# Sensor_Board_v2.net
KiCad netlist of a schematic drawn in EAGLE
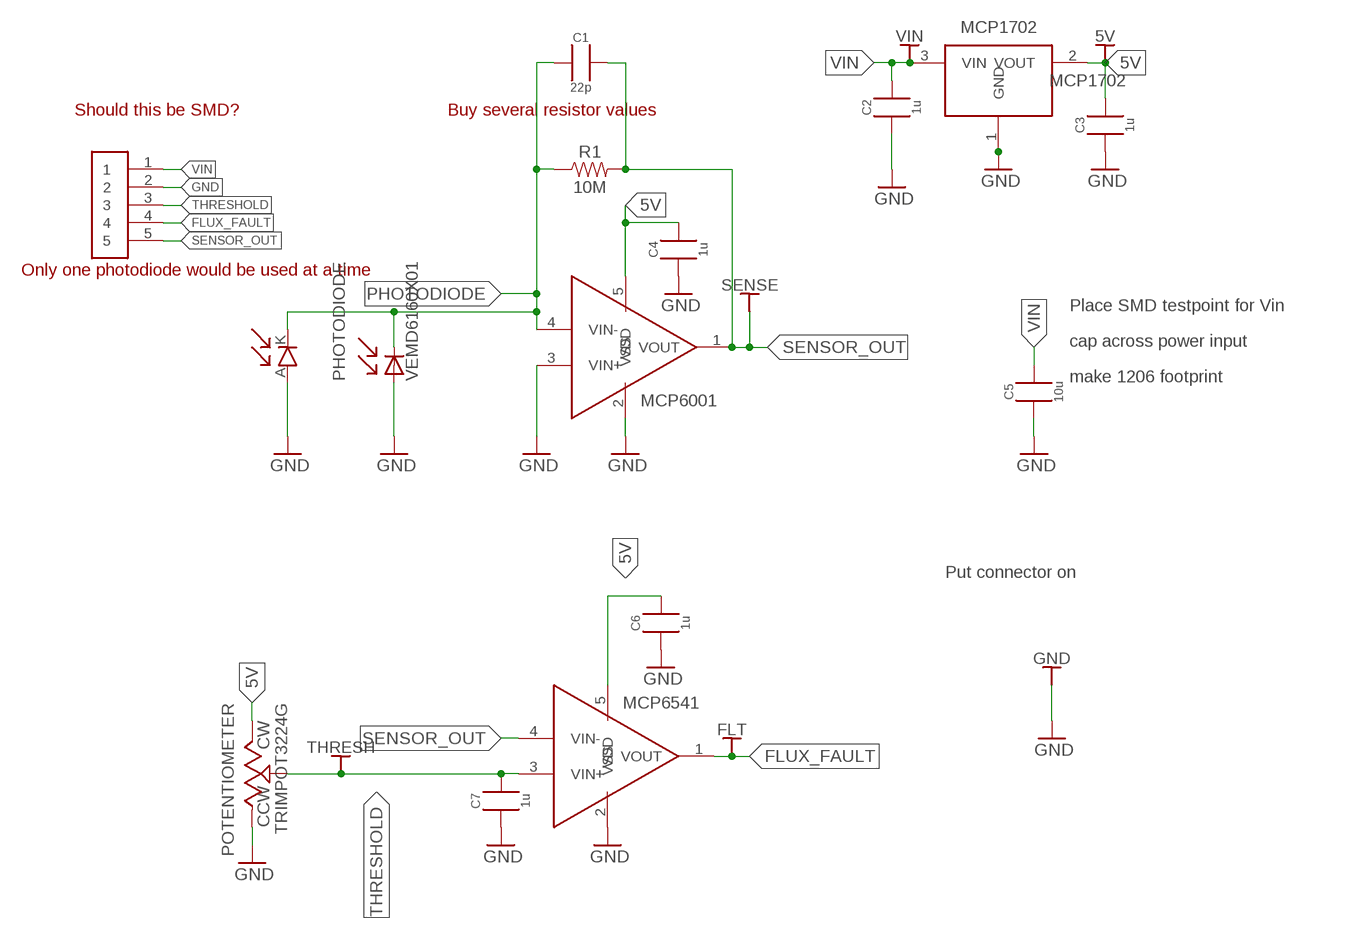
[diagram p0: schematic, sheet 1]

(export (version "E")
  (design (tool "Eeschema 10.0.6"))
  (components
    (comp (ref "5V")
      (value "TEST_POINT5015")
      (footprint "eagle-import:5015")
      (libsource (lib "eagle-import") (part "TEST_POINT5015"))
    )
    (comp (ref "C1")
      (value "22p")
      (footprint "eagle-import:0805_C")
      (libsource (lib "eagle-import") (part "CAP0805C"))
    )
    (comp (ref "C2")
      (value "1u")
      (footprint "eagle-import:0805_C")
      (libsource (lib "eagle-import") (part "CAP0805C"))
    )
    (comp (ref "C3")
      (value "1u")
      (footprint "eagle-import:0805_B")
      (libsource (lib "eagle-import") (part "CAP805B"))
    )
    (comp (ref "C4")
      (value "1u")
      (footprint "eagle-import:0805_B")
      (libsource (lib "eagle-import") (part "CAP805B"))
    )
    (comp (ref "C5")
      (value "10u")
      (footprint "eagle-import:1206_A")
      (libsource (lib "eagle-import") (part "CAP1206A"))
    )
    (comp (ref "C6")
      (value "1u")
      (footprint "eagle-import:0805_B")
      (libsource (lib "eagle-import") (part "CAP805B"))
    )
    (comp (ref "C7")
      (value "1u")
      (footprint "eagle-import:0805_B")
      (libsource (lib "eagle-import") (part "CAP805B"))
    )
    (comp (ref "FLT")
      (value "TEST_POINT5015")
      (footprint "eagle-import:5015")
      (libsource (lib "eagle-import") (part "TEST_POINT5015"))
    )
    (comp (ref "GND")
      (value "TEST_POINT5015")
      (footprint "eagle-import:5015")
      (libsource (lib "eagle-import") (part "TEST_POINT5015"))
    )
    (comp (ref "MCP1702")
      (value "MCP1702")
      (footprint "eagle-import:SOT23A(CB)")
      (libsource (lib "eagle-import") (part "MCP1702"))
    )
    (comp (ref "MCP6001")
      (value "MCP6001MCP6001")
      (footprint "eagle-import:SOT23(OT)")
      (libsource (lib "eagle-import") (part "MCP6001MCP6001"))
    )
    (comp (ref "MCP6541")
      (value "MCP6541")
      (footprint "eagle-import:SOT23(OT)")
      (libsource (lib "eagle-import") (part "MCP6541"))
    )
    (comp (ref "PHOTODIODE")
      (value "VEMD6160X01")
      (footprint "eagle-import:VEMD6160X01")
      (libsource (lib "eagle-import") (part "VEMD6160X01"))
    )
    (comp (ref "R1")
      (value "10M")
      (footprint "eagle-import:1206")
      (libsource (lib "eagle-import") (part "RESISTOR1206"))
    )
    (comp (ref "SENSE")
      (value "TEST_POINT5015")
      (footprint "eagle-import:5015")
      (libsource (lib "eagle-import") (part "TEST_POINT5015"))
    )
    (comp (ref "THRESH")
      (value "TEST_POINT5015")
      (footprint "eagle-import:5015")
      (libsource (lib "eagle-import") (part "TEST_POINT5015"))
    )
    (comp (ref "TRIMPOT3224G")
      (value "POTENTIOMETER")
      (footprint "eagle-import:3224G")
      (libsource (lib "eagle-import") (part "POTENTIOMETER"))
    )
    (comp (ref "U$1")
      (value "M05OSTVN05")
      (footprint "eagle-import:OSTVN05")
      (libsource (lib "eagle-import") (part "M05OSTVN05"))
    )
    (comp (ref "U$2")
      (value "PHOTODIODE")
      (footprint "eagle-import:LTR-516AD")
      (libsource (lib "eagle-import") (part "PHOTODIODE"))
    )
    (comp (ref "VIN")
      (value "TEST_POINT5015")
      (footprint "eagle-import:5015")
      (libsource (lib "eagle-import") (part "TEST_POINT5015"))
    )
  )
  (nets
    (net (code "1") (name "5V") (class "Default")
      (node (ref "5V") (pin "1") (pinfunction "P$1_1") (pintype "bidirectional"))
      (node (ref "C3") (pin "2") (pinfunction "2_2") (pintype "bidirectional"))
      (node (ref "C4") (pin "2") (pinfunction "2_2") (pintype "bidirectional"))
      (node (ref "C6") (pin "2") (pinfunction "2_2") (pintype "bidirectional"))
      (node (ref "MCP1702") (pin "2") (pinfunction "VOUT_2") (pintype "power_in"))
      (node (ref "MCP6001") (pin "5") (pinfunction "VDD_5") (pintype "power_in"))
      (node (ref "MCP6541") (pin "5") (pinfunction "VDD_5") (pintype "power_in"))
      (node (ref "TRIMPOT3224G") (pin "3") (pinfunction "CW_3") (pintype "passive"))
    )
    (net (code "2") (name "FLUX_FAULT") (class "Default")
      (node (ref "FLT") (pin "1") (pinfunction "P$1_1") (pintype "bidirectional"))
      (node (ref "MCP6541") (pin "1") (pinfunction "VOUT_1") (pintype "output"))
      (node (ref "U$1") (pin "4") (pinfunction "4_4") (pintype "bidirectional"))
    )
    (net (code "3") (name "GND") (class "Default")
      (node (ref "C2") (pin "1") (pinfunction "1_1") (pintype "bidirectional"))
      (node (ref "C3") (pin "1") (pinfunction "1_1") (pintype "bidirectional"))
      (node (ref "C4") (pin "1") (pinfunction "1_1") (pintype "bidirectional"))
      (node (ref "C5") (pin "1") (pinfunction "1_1") (pintype "bidirectional"))
      (node (ref "C6") (pin "1") (pinfunction "1_1") (pintype "bidirectional"))
      (node (ref "C7") (pin "1") (pinfunction "1_1") (pintype "bidirectional"))
      (node (ref "GND") (pin "1") (pinfunction "P$1_1") (pintype "bidirectional"))
      (node (ref "MCP1702") (pin "1") (pinfunction "GND_1") (pintype "power_in"))
      (node (ref "MCP6001") (pin "2") (pinfunction "VSS_2") (pintype "power_in"))
      (node (ref "MCP6001") (pin "3") (pinfunction "VIN+_3") (pintype "input"))
      (node (ref "MCP6541") (pin "2") (pinfunction "VSS_2") (pintype "power_in"))
      (node (ref "PHOTODIODE") (pin "A1") (pinfunction "A_A1") (pintype "passive"))
      (node (ref "TRIMPOT3224G") (pin "1") (pinfunction "CCW_1") (pintype "passive"))
      (node (ref "U$1") (pin "2") (pinfunction "2_2") (pintype "bidirectional"))
      (node (ref "U$2") (pin "A") (pinfunction "A_A") (pintype "power_in"))
    )
    (net (code "4") (name "PHOTODIODE") (class "Default")
      (node (ref "C1") (pin "1") (pinfunction "1_1") (pintype "bidirectional"))
      (node (ref "MCP6001") (pin "4") (pinfunction "VIN-_4") (pintype "input"))
      (node (ref "PHOTODIODE") (pin "K") (pinfunction "C_K") (pintype "passive"))
      (node (ref "R1") (pin "1") (pinfunction "1_1") (pintype "passive"))
      (node (ref "U$2") (pin "K") (pinfunction "C_K") (pintype "power_in"))
    )
    (net (code "5") (name "SENSOR_OUT") (class "Default")
      (node (ref "C1") (pin "2") (pinfunction "2_2") (pintype "bidirectional"))
      (node (ref "MCP6001") (pin "1") (pinfunction "VOUT_1") (pintype "output"))
      (node (ref "MCP6541") (pin "4") (pinfunction "VIN-_4") (pintype "input"))
      (node (ref "R1") (pin "2") (pinfunction "2_2") (pintype "passive"))
      (node (ref "SENSE") (pin "1") (pinfunction "P$1_1") (pintype "bidirectional"))
      (node (ref "U$1") (pin "5") (pinfunction "5_5") (pintype "bidirectional"))
    )
    (net (code "6") (name "THRESHOLD") (class "Default")
      (node (ref "C7") (pin "2") (pinfunction "2_2") (pintype "bidirectional"))
      (node (ref "MCP6541") (pin "3") (pinfunction "VIN+_3") (pintype "input"))
      (node (ref "THRESH") (pin "1") (pinfunction "P$1_1") (pintype "bidirectional"))
      (node (ref "TRIMPOT3224G") (pin "2") (pinfunction "WIPER_2") (pintype "passive"))
      (node (ref "U$1") (pin "3") (pinfunction "3_3") (pintype "bidirectional"))
    )
    (net (code "7") (name "VIN") (class "Default")
      (node (ref "C2") (pin "2") (pinfunction "2_2") (pintype "bidirectional"))
      (node (ref "C5") (pin "2") (pinfunction "2_2") (pintype "bidirectional"))
      (node (ref "MCP1702") (pin "3") (pinfunction "VIN_3") (pintype "power_in"))
      (node (ref "U$1") (pin "1") (pinfunction "1_1") (pintype "bidirectional"))
      (node (ref "VIN") (pin "1") (pinfunction "P$1_1") (pintype "bidirectional"))
    )
  )
)
